# Stethi_v2.net
KiCad netlist of a schematic drawn in EAGLE
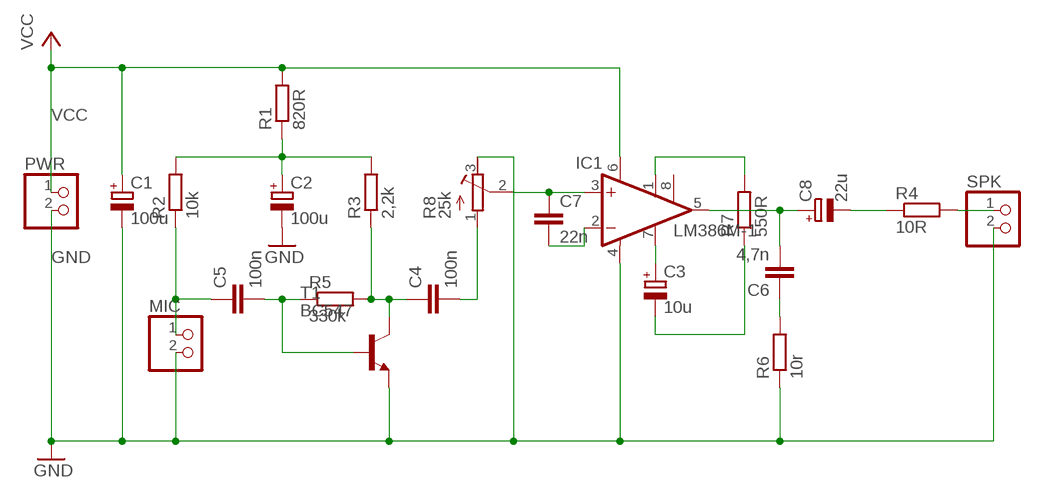
[diagram p0: schematic, sheet 1]

(export (version "E")
  (design (tool "Eeschema 10.0.6"))
  (components
    (comp (ref "C1")
      (value "100u")
      (footprint "eagle-import:D_7343-31R")
      (libsource (lib "eagle-import") (part "CPOL-EUD/7343-31R"))
    )
    (comp (ref "C2")
      (value "100u")
      (footprint "eagle-import:D_7343-31R")
      (libsource (lib "eagle-import") (part "CPOL-EUD/7343-31R"))
    )
    (comp (ref "C3")
      (value "10u")
      (footprint "eagle-import:A_3216-18R")
      (libsource (lib "eagle-import") (part "CPOL-EUA/3216-18R"))
    )
    (comp (ref "C4")
      (value "100n")
      (footprint "eagle-import:C0805K")
      (libsource (lib "eagle-import") (part "C-EUC0805K"))
    )
    (comp (ref "C5")
      (value "100n")
      (footprint "eagle-import:C0805K")
      (libsource (lib "eagle-import") (part "C-EUC0805K"))
    )
    (comp (ref "C6")
      (value "4,7n")
      (footprint "eagle-import:C0805K")
      (libsource (lib "eagle-import") (part "C-EUC0805K"))
    )
    (comp (ref "C7")
      (value "22n")
      (footprint "eagle-import:C0805K")
      (libsource (lib "eagle-import") (part "C-EUC0805K"))
    )
    (comp (ref "C8")
      (value "22u")
      (footprint "eagle-import:A_3216-18R")
      (libsource (lib "eagle-import") (part "CPOL-EUA/3216-18R"))
    )
    (comp (ref "IC1")
      (value "LM386M-1")
      (footprint "eagle-import:SO08")
      (libsource (lib "eagle-import") (part "LM386?-M1"))
    )
    (comp (ref "MIC")
      (value "PINHD-1X2")
      (footprint "eagle-import:1X02")
      (libsource (lib "eagle-import") (part "PINHD-1X2"))
    )
    (comp (ref "PWR")
      (value "PINHD-1X2")
      (footprint "eagle-import:1X02")
      (libsource (lib "eagle-import") (part "PINHD-1X2"))
    )
    (comp (ref "R1")
      (value "820R")
      (footprint "eagle-import:R0805")
      (libsource (lib "eagle-import") (part "R-EU_R0805"))
    )
    (comp (ref "R2")
      (value "10k")
      (footprint "eagle-import:R0805")
      (libsource (lib "eagle-import") (part "R-EU_R0805"))
    )
    (comp (ref "R3")
      (value "2,2k")
      (footprint "eagle-import:R0805")
      (libsource (lib "eagle-import") (part "R-EU_R0805"))
    )
    (comp (ref "R4")
      (value "10R")
      (footprint "eagle-import:R0805")
      (libsource (lib "eagle-import") (part "R-EU_R0805"))
    )
    (comp (ref "R5")
      (value "330k")
      (footprint "eagle-import:R0805")
      (libsource (lib "eagle-import") (part "R-EU_R0805"))
    )
    (comp (ref "R6")
      (value "10r")
      (footprint "eagle-import:R0805")
      (libsource (lib "eagle-import") (part "R-EU_R0805"))
    )
    (comp (ref "R7")
      (value "550R")
      (footprint "eagle-import:R0805")
      (libsource (lib "eagle-import") (part "R-EU_R0805"))
    )
    (comp (ref "R8")
      (value "25k")
      (footprint "eagle-import:RTRIM5X")
      (libsource (lib "eagle-import") (part "R-TRIMM5X"))
    )
    (comp (ref "SPK")
      (value "PINHD-1X2")
      (footprint "eagle-import:1X02")
      (libsource (lib "eagle-import") (part "PINHD-1X2"))
    )
    (comp (ref "T1")
      (value "BC547")
      (footprint "eagle-import:SOT23")
      (libsource (lib "eagle-import") (part "BC847"))
    )
  )
  (nets
    (net (code "1") (name "GND") (class "Default")
      (node (ref "C1") (pin "-") (pinfunction "-_-") (pintype "passive"))
      (node (ref "C2") (pin "-") (pinfunction "-_-") (pintype "passive"))
      (node (ref "IC1") (pin "4") (pinfunction "GND_4") (pintype "power_in"))
      (node (ref "MIC") (pin "2") (pinfunction "2_2") (pintype "passive"))
      (node (ref "PWR") (pin "2") (pinfunction "2_2") (pintype "passive"))
      (node (ref "R6") (pin "1") (pinfunction "1_1") (pintype "passive"))
      (node (ref "R8") (pin "3") (pinfunction "E_3") (pintype "passive"))
      (node (ref "SPK") (pin "2") (pinfunction "2_2") (pintype "passive"))
      (node (ref "T1") (pin "2") (pinfunction "E_2") (pintype "passive"))
    )
    (net (code "2") (name "Net-(C2-Pad+)") (class "Default")
      (node (ref "C2") (pin "+") (pinfunction "+_+") (pintype "passive"))
      (node (ref "R1") (pin "1") (pinfunction "1_1") (pintype "passive"))
      (node (ref "R2") (pin "2") (pinfunction "2_2") (pintype "passive"))
      (node (ref "R3") (pin "2") (pinfunction "2_2") (pintype "passive"))
    )
    (net (code "3") (name "Net-(C3-Pad-)") (class "Default")
      (node (ref "C3") (pin "-") (pinfunction "-_-") (pintype "passive"))
      (node (ref "R7") (pin "1") (pinfunction "1_1") (pintype "passive"))
    )
    (net (code "4") (name "Net-(C5-Pad1)") (class "Default")
      (node (ref "C5") (pin "1") (pinfunction "1_1") (pintype "passive"))
      (node (ref "MIC") (pin "1") (pinfunction "1_1") (pintype "passive"))
      (node (ref "R2") (pin "1") (pinfunction "1_1") (pintype "passive"))
    )
    (net (code "5") (name "Net-(C6-Pad1)") (class "Default")
      (node (ref "C6") (pin "1") (pinfunction "1_1") (pintype "passive"))
      (node (ref "R6") (pin "2") (pinfunction "2_2") (pintype "passive"))
    )
    (net (code "6") (name "Net-(C8-Pad-)") (class "Default")
      (node (ref "C8") (pin "-") (pinfunction "-_-") (pintype "passive"))
      (node (ref "R4") (pin "1") (pinfunction "1_1") (pintype "passive"))
    )
    (net (code "7") (name "Net-(IC1-+IN)") (class "Default")
      (node (ref "C7") (pin "1") (pinfunction "1_1") (pintype "passive"))
      (node (ref "IC1") (pin "3") (pinfunction "+IN_3") (pintype "input"))
      (node (ref "R8") (pin "2") (pinfunction "S_2") (pintype "passive"))
    )
    (net (code "8") (name "Net-(IC1--IN)") (class "Default")
      (node (ref "C7") (pin "2") (pinfunction "2_2") (pintype "passive"))
      (node (ref "IC1") (pin "2") (pinfunction "-IN_2") (pintype "input"))
    )
    (net (code "9") (name "Net-(IC1-BYPASS)") (class "Default")
      (node (ref "C3") (pin "+") (pinfunction "+_+") (pintype "passive"))
      (node (ref "IC1") (pin "7") (pinfunction "BYPASS_7") (pintype "passive"))
    )
    (net (code "10") (name "Net-(IC1-GAIN-Pad1)") (class "Default")
      (node (ref "IC1") (pin "1") (pinfunction "GAIN_1") (pintype "passive"))
      (node (ref "R7") (pin "2") (pinfunction "2_2") (pintype "passive"))
    )
    (net (code "11") (name "Net-(IC1-OUT)") (class "Default")
      (node (ref "C6") (pin "2") (pinfunction "2_2") (pintype "passive"))
      (node (ref "C8") (pin "+") (pinfunction "+_+") (pintype "passive"))
      (node (ref "IC1") (pin "5") (pinfunction "OUT_5") (pintype "output"))
    )
    (net (code "12") (name "Net-(R4-Pad2)") (class "Default")
      (node (ref "R4") (pin "2") (pinfunction "2_2") (pintype "passive"))
      (node (ref "SPK") (pin "1") (pinfunction "1_1") (pintype "passive"))
    )
    (net (code "13") (name "Net-(R8-A)") (class "Default")
      (node (ref "C4") (pin "2") (pinfunction "2_2") (pintype "passive"))
      (node (ref "R8") (pin "1") (pinfunction "A_1") (pintype "passive"))
    )
    (net (code "14") (name "Net-(T1-B)") (class "Default")
      (node (ref "C5") (pin "2") (pinfunction "2_2") (pintype "passive"))
      (node (ref "R5") (pin "1") (pinfunction "1_1") (pintype "passive"))
      (node (ref "T1") (pin "1") (pinfunction "B_1") (pintype "passive"))
    )
    (net (code "15") (name "Net-(T1-C)") (class "Default")
      (node (ref "C4") (pin "1") (pinfunction "1_1") (pintype "passive"))
      (node (ref "R3") (pin "1") (pinfunction "1_1") (pintype "passive"))
      (node (ref "R5") (pin "2") (pinfunction "2_2") (pintype "passive"))
      (node (ref "T1") (pin "3") (pinfunction "C_3") (pintype "passive"))
    )
    (net (code "16") (name "VCC") (class "Default")
      (node (ref "C1") (pin "+") (pinfunction "+_+") (pintype "passive"))
      (node (ref "IC1") (pin "6") (pinfunction "VS_6") (pintype "power_in"))
      (node (ref "PWR") (pin "1") (pinfunction "1_1") (pintype "passive"))
      (node (ref "R1") (pin "2") (pinfunction "2_2") (pintype "passive"))
    )
    (net (code "17") (name "unconnected-(IC1-GAIN-Pad8)") (class "Default")
      (node (ref "IC1") (pin "8") (pinfunction "GAIN_8") (pintype "passive"))
    )
  )
)
